# Wireless_Charging.net
KiCad netlist of a schematic drawn in Altium Designer
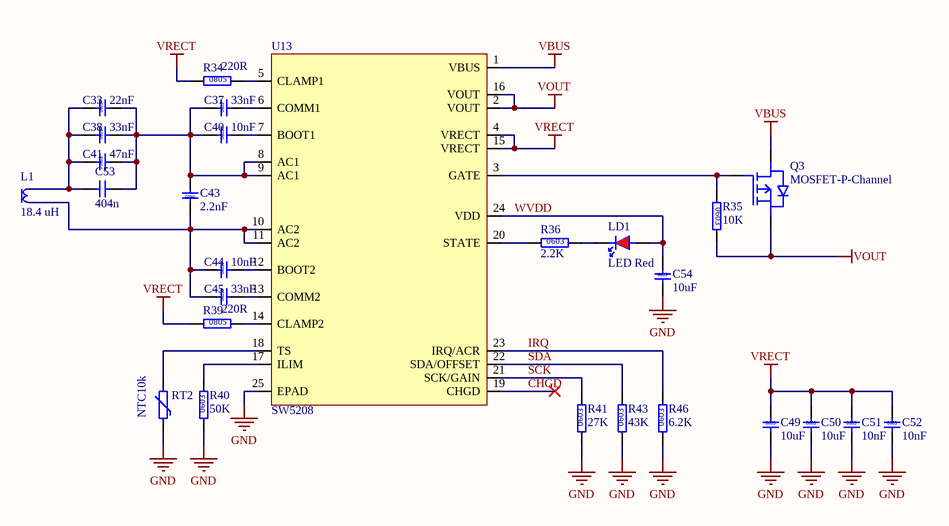
[diagram p0: Wireless Charging.SchDoc]

(export (version "E")
  (design (tool "Eeschema 10.0.6"))
  (components
    (comp (ref "C33")
      (value "22nF")
      (footprint "C0603")
      (description "10% 50V")
      (fields (field (name "PART NO") "W-T-CA-X703N10K50VNT"))
      (libsource (lib "Rescap") (part "C 0603 10nF 50V"))
    )
    (comp (ref "C37")
      (value "33nF")
      (footprint "C0603")
      (description "10% 50V")
      (fields (field (name "PART NO") "W-T-CA-X703N10K50VNT"))
      (libsource (lib "Rescap") (part "C 0603 10nF 50V"))
    )
    (comp (ref "C38")
      (value "33nF")
      (footprint "C0603")
      (description "10% 50V")
      (fields (field (name "PART NO") "W-T-CA-X703N10K50VNT"))
      (libsource (lib "Rescap") (part "C 0603 10nF 50V"))
    )
    (comp (ref "C40")
      (value "10nF")
      (footprint "C0603")
      (description "10% 50V")
      (fields (field (name "PART NO") "W-T-CA-X703N10K50VNT"))
      (libsource (lib "Rescap") (part "C 0603 10nF 50V"))
    )
    (comp (ref "C41")
      (value "47nF")
      (footprint "C0603")
      (description "10% 50V")
      (fields (field (name "PART NO") "W-T-CA-X703N10K50VNT"))
      (libsource (lib "Rescap") (part "C 0603 10nF 50V"))
    )
    (comp (ref "C43")
      (value "2.2nF")
      (footprint "C0603")
      (description "10% 50V")
      (fields (field (name "PART NO") "WP0005364"))
      (libsource (lib "Rescap") (part "C 0603 2.2nF 50V"))
    )
    (comp (ref "C44")
      (value "10nF")
      (footprint "C0603")
      (description "10% 50V")
      (fields (field (name "PART NO") "W-T-CA-X703N10K50VNT"))
      (libsource (lib "Rescap") (part "C 0603 10nF 50V"))
    )
    (comp (ref "C45")
      (value "33nF")
      (footprint "C0603")
      (description "10% 50V")
      (fields (field (name "PART NO") "W-T-CA-X703N10K50VNT"))
      (libsource (lib "Rescap") (part "C 0603 10nF 50V"))
    )
    (comp (ref "C49")
      (value "10uF")
      (footprint "C0805")
      (description "10% 25V")
      (fields (field (name "PART NO") "WP0005368"))
      (libsource (lib "Rescap") (part "C 0805 10uF 25V"))
    )
    (comp (ref "C50")
      (value "10uF")
      (footprint "C0805")
      (description "10% 25V")
      (fields (field (name "PART NO") "WP0005368"))
      (libsource (lib "Rescap") (part "C 0805 10uF 25V"))
    )
    (comp (ref "C51")
      (value "10nF")
      (footprint "C0603")
      (description "10% 50V")
      (fields (field (name "PART NO") "W-T-CA-X703N10K50VNT"))
      (libsource (lib "Rescap") (part "C 0603 10nF 50V"))
    )
    (comp (ref "C52")
      (value "10nF")
      (footprint "C0603")
      (description "10% 50V")
      (fields (field (name "PART NO") "W-T-CA-X703N10K50VNT"))
      (libsource (lib "Rescap") (part "C 0603 10nF 50V"))
    )
    (comp (ref "C53")
      (value "404n")
      (footprint "CBB Capacitor-7.1mm-WO3D")
      (description "CBB Capacitor 404n 100V")
      (libsource (lib "Capacitors") (part "Capacitor"))
    )
    (comp (ref "C54")
      (value "10uF")
      (footprint "C0805")
      (description "10% 25V")
      (fields (field (name "PART NO") "WP0005368"))
      (libsource (lib "Rescap") (part "C 0805 10uF 25V"))
    )
    (comp (ref "L1")
      (value "18.4 uH")
      (footprint "SMD PAD 1x2")
      (description "SMD Inductor")
      (libsource (lib "Inductor") (part "Wcoil"))
    )
    (comp (ref "LD1")
      (value "LED Red")
      (footprint "LED-0603-RED")
      (libsource (lib "Optoelectronics") (part "LED Red"))
    )
    (comp (ref "Q3")
      (value "MOSFET-P-Channel")
      (footprint "PMOS-SOT23")
      (libsource (lib "Transistor") (part "MOSFET-P-Channel"))
    )
    (comp (ref "R34")
      (value "220R")
      (footprint "R0805-LD")
      (description "5%")
      (fields (field (name "PART NO") "W-T-RE-RS05K121JT"))
      (libsource (lib "Rescap") (part "R 0805 120R"))
    )
    (comp (ref "R35")
      (value "10K")
      (footprint "R0603-LD")
      (description "5%")
      (fields (field (name "PART NO") "W-T-RE-RS03K103JT") (field (name "MANUFACTURER") "热敏D541V11增加1颗用量"))
      (libsource (lib "Rescap") (part "R 0603 10K"))
    )
    (comp (ref "R36")
      (value "2.2K")
      (footprint "R0603-LD")
      (description "5%")
      (fields (field (name "PART NO") "W-T-RE-RS03K272JT"))
      (libsource (lib "Rescap") (part "R 0603 2.7K"))
    )
    (comp (ref "R39")
      (value "220R")
      (footprint "R0805-LD")
      (description "5%")
      (fields (field (name "PART NO") "W-T-RE-RS05K121JT"))
      (libsource (lib "Rescap") (part "R 0805 120R"))
    )
    (comp (ref "R40")
      (value "50K")
      (footprint "R0603-LD")
      (description "1%")
      (fields (field (name "PART NO") "WP0005360"))
      (libsource (lib "Rescap") (part "R 0603 51K"))
    )
    (comp (ref "R41")
      (value "27K")
      (footprint "R0603-LD")
      (description "1%")
      (fields (field (name "PART NO") "W-T-RE-RS03K202FT"))
      (libsource (lib "Rescap") (part "R 0603 2K"))
    )
    (comp (ref "R43")
      (value "43K")
      (footprint "R0603-LD")
      (description "1%")
      (fields (field (name "PART NO") "W-T-RE-RS03K202FT"))
      (libsource (lib "Rescap") (part "R 0603 2K"))
    )
    (comp (ref "R46")
      (value "6.2K")
      (footprint "R0603-LD")
      (description "1%")
      (fields (field (name "PART NO") "W-T-RE-RS03K202FT"))
      (libsource (lib "Rescap") (part "R 0603 2K"))
    )
    (comp (ref "RT2") (value "NTC10k") (footprint "RT0603") (libsource (lib "Sensor") (part "Thermistor")))
    (comp (ref "U13")
      (value "SW5208")
      (footprint "QFN-24-4x4-0.5P")
      (libsource (lib "mylib2") (part "SW5208"))
    )
  )
  (nets
    (net (code "1") (name "/CHGD") (class "Default")
      (node (ref "U13") (pin "19") (pinfunction "CHGD_19") (pintype "passive+no_connect"))
    )
    (net (code "2") (name "/IRQ") (class "Default")
      (node (ref "R46") (pin "2") (pinfunction "2_2") (pintype "passive"))
      (node (ref "U13") (pin "23") (pinfunction "IRQ/ACR_23") (pintype "passive"))
    )
    (net (code "3") (name "/SCK") (class "Default")
      (node (ref "R41") (pin "2") (pinfunction "2_2") (pintype "passive"))
      (node (ref "U13") (pin "21") (pinfunction "SCK/GAIN_21") (pintype "passive"))
    )
    (net (code "4") (name "/SDA") (class "Default")
      (node (ref "R43") (pin "2") (pinfunction "2_2") (pintype "passive"))
      (node (ref "U13") (pin "22") (pinfunction "SDA/OFFSET_22") (pintype "passive"))
    )
    (net (code "5") (name "/WVDD") (class "Default")
      (node (ref "C54") (pin "1") (pinfunction "1_1") (pintype "passive"))
      (node (ref "LD1") (pin "1") (pinfunction "A_1") (pintype "passive"))
      (node (ref "U13") (pin "24") (pinfunction "VDD_24") (pintype "passive"))
    )
    (net (code "6") (name "GND") (class "Default")
      (node (ref "C49") (pin "2") (pinfunction "2_2") (pintype "passive"))
      (node (ref "C50") (pin "2") (pinfunction "2_2") (pintype "passive"))
      (node (ref "C51") (pin "2") (pinfunction "2_2") (pintype "passive"))
      (node (ref "C52") (pin "2") (pinfunction "2_2") (pintype "passive"))
      (node (ref "C54") (pin "2") (pinfunction "2_2") (pintype "passive"))
      (node (ref "R40") (pin "1") (pinfunction "1_1") (pintype "passive"))
      (node (ref "R41") (pin "1") (pinfunction "1_1") (pintype "passive"))
      (node (ref "R43") (pin "1") (pinfunction "1_1") (pintype "passive"))
      (node (ref "R46") (pin "1") (pinfunction "1_1") (pintype "passive"))
      (node (ref "RT2") (pin "1") (pinfunction "1_1") (pintype "passive"))
      (node (ref "U13") (pin "25") (pinfunction "EPAD_25") (pintype "passive"))
    )
    (net (code "7") (name "Net-(C33-Pad1)") (class "Default")
      (node (ref "C33") (pin "1") (pinfunction "1_1") (pintype "passive"))
      (node (ref "C38") (pin "1") (pinfunction "1_1") (pintype "passive"))
      (node (ref "C41") (pin "1") (pinfunction "1_1") (pintype "passive"))
      (node (ref "C53") (pin "2") (pinfunction "2_2") (pintype "passive"))
      (node (ref "L1") (pin "2") (pinfunction "2_2") (pintype "passive"))
    )
    (net (code "8") (name "Net-(C33-Pad2)") (class "Default")
      (node (ref "C33") (pin "2") (pinfunction "2_2") (pintype "passive"))
      (node (ref "C37") (pin "1") (pinfunction "1_1") (pintype "passive"))
      (node (ref "C38") (pin "2") (pinfunction "2_2") (pintype "passive"))
      (node (ref "C40") (pin "1") (pinfunction "1_1") (pintype "passive"))
      (node (ref "C41") (pin "2") (pinfunction "2_2") (pintype "passive"))
      (node (ref "C43") (pin "2") (pinfunction "2_2") (pintype "passive"))
      (node (ref "C53") (pin "1") (pinfunction "1_1") (pintype "passive"))
      (node (ref "U13") (pin "8") (pinfunction "AC1_8") (pintype "passive"))
      (node (ref "U13") (pin "9") (pinfunction "AC1_9") (pintype "passive"))
    )
    (net (code "9") (name "Net-(C43-Pad1)") (class "Default")
      (node (ref "C43") (pin "1") (pinfunction "1_1") (pintype "passive"))
      (node (ref "C44") (pin "1") (pinfunction "1_1") (pintype "passive"))
      (node (ref "C45") (pin "1") (pinfunction "1_1") (pintype "passive"))
      (node (ref "L1") (pin "1") (pinfunction "1_1") (pintype "passive"))
      (node (ref "U13") (pin "10") (pinfunction "AC2_10") (pintype "passive"))
      (node (ref "U13") (pin "11") (pinfunction "AC2_11") (pintype "passive"))
    )
    (net (code "10") (name "Net-(LD1-K)") (class "Default")
      (node (ref "LD1") (pin "2") (pinfunction "K_2") (pintype "passive"))
      (node (ref "R36") (pin "2") (pinfunction "2_2") (pintype "passive"))
    )
    (net (code "11") (name "Net-(Q3-G)") (class "Default")
      (node (ref "Q3") (pin "1") (pinfunction "G_1") (pintype "passive"))
      (node (ref "R35") (pin "1") (pinfunction "1_1") (pintype "passive"))
      (node (ref "U13") (pin "3") (pinfunction "GATE_3") (pintype "passive"))
    )
    (net (code "12") (name "Net-(U13-BOOT1)") (class "Default")
      (node (ref "C40") (pin "2") (pinfunction "2_2") (pintype "passive"))
      (node (ref "U13") (pin "7") (pinfunction "BOOT1_7") (pintype "passive"))
    )
    (net (code "13") (name "Net-(U13-BOOT2)") (class "Default")
      (node (ref "C44") (pin "2") (pinfunction "2_2") (pintype "passive"))
      (node (ref "U13") (pin "12") (pinfunction "BOOT2_12") (pintype "passive"))
    )
    (net (code "14") (name "Net-(U13-CLAMP1)") (class "Default")
      (node (ref "R34") (pin "2") (pinfunction "2_2") (pintype "passive"))
      (node (ref "U13") (pin "5") (pinfunction "CLAMP1_5") (pintype "passive"))
    )
    (net (code "15") (name "Net-(U13-CLAMP2)") (class "Default")
      (node (ref "R39") (pin "2") (pinfunction "2_2") (pintype "passive"))
      (node (ref "U13") (pin "14") (pinfunction "CLAMP2_14") (pintype "passive"))
    )
    (net (code "16") (name "Net-(U13-COMM1)") (class "Default")
      (node (ref "C37") (pin "2") (pinfunction "2_2") (pintype "passive"))
      (node (ref "U13") (pin "6") (pinfunction "COMM1_6") (pintype "passive"))
    )
    (net (code "17") (name "Net-(U13-COMM2)") (class "Default")
      (node (ref "C45") (pin "2") (pinfunction "2_2") (pintype "passive"))
      (node (ref "U13") (pin "13") (pinfunction "COMM2_13") (pintype "passive"))
    )
    (net (code "18") (name "Net-(U13-ILIM)") (class "Default")
      (node (ref "R40") (pin "2") (pinfunction "2_2") (pintype "passive"))
      (node (ref "U13") (pin "17") (pinfunction "ILIM_17") (pintype "passive"))
    )
    (net (code "19") (name "Net-(U13-STATE)") (class "Default")
      (node (ref "R36") (pin "1") (pinfunction "1_1") (pintype "passive"))
      (node (ref "U13") (pin "20") (pinfunction "STATE_20") (pintype "passive"))
    )
    (net (code "20") (name "Net-(U13-TS)") (class "Default")
      (node (ref "RT2") (pin "2") (pinfunction "2_2") (pintype "passive"))
      (node (ref "U13") (pin "18") (pinfunction "TS_18") (pintype "passive"))
    )
    (net (code "21") (name "VBUS") (class "Default")
      (node (ref "Q3") (pin "2") (pinfunction "D_2") (pintype "passive"))
      (node (ref "U13") (pin "1") (pinfunction "VBUS_1") (pintype "passive"))
    )
    (net (code "22") (name "VOUT") (class "Default")
      (node (ref "Q3") (pin "3") (pinfunction "S_3") (pintype "passive"))
      (node (ref "R35") (pin "2") (pinfunction "2_2") (pintype "passive"))
      (node (ref "U13") (pin "16") (pinfunction "VOUT_16") (pintype "passive"))
      (node (ref "U13") (pin "2") (pinfunction "VOUT_2") (pintype "passive"))
    )
    (net (code "23") (name "VRECT") (class "Default")
      (node (ref "C49") (pin "1") (pinfunction "1_1") (pintype "passive"))
      (node (ref "C50") (pin "1") (pinfunction "1_1") (pintype "passive"))
      (node (ref "C51") (pin "1") (pinfunction "1_1") (pintype "passive"))
      (node (ref "C52") (pin "1") (pinfunction "1_1") (pintype "passive"))
      (node (ref "R34") (pin "1") (pinfunction "1_1") (pintype "passive"))
      (node (ref "R39") (pin "1") (pinfunction "1_1") (pintype "passive"))
      (node (ref "U13") (pin "15") (pinfunction "VRECT_15") (pintype "passive"))
      (node (ref "U13") (pin "4") (pinfunction "VRECT_4") (pintype "passive"))
    )
  )
)
